# MCU063B_Emulator.net
KiCad netlist of a schematic drawn in Altium Designer
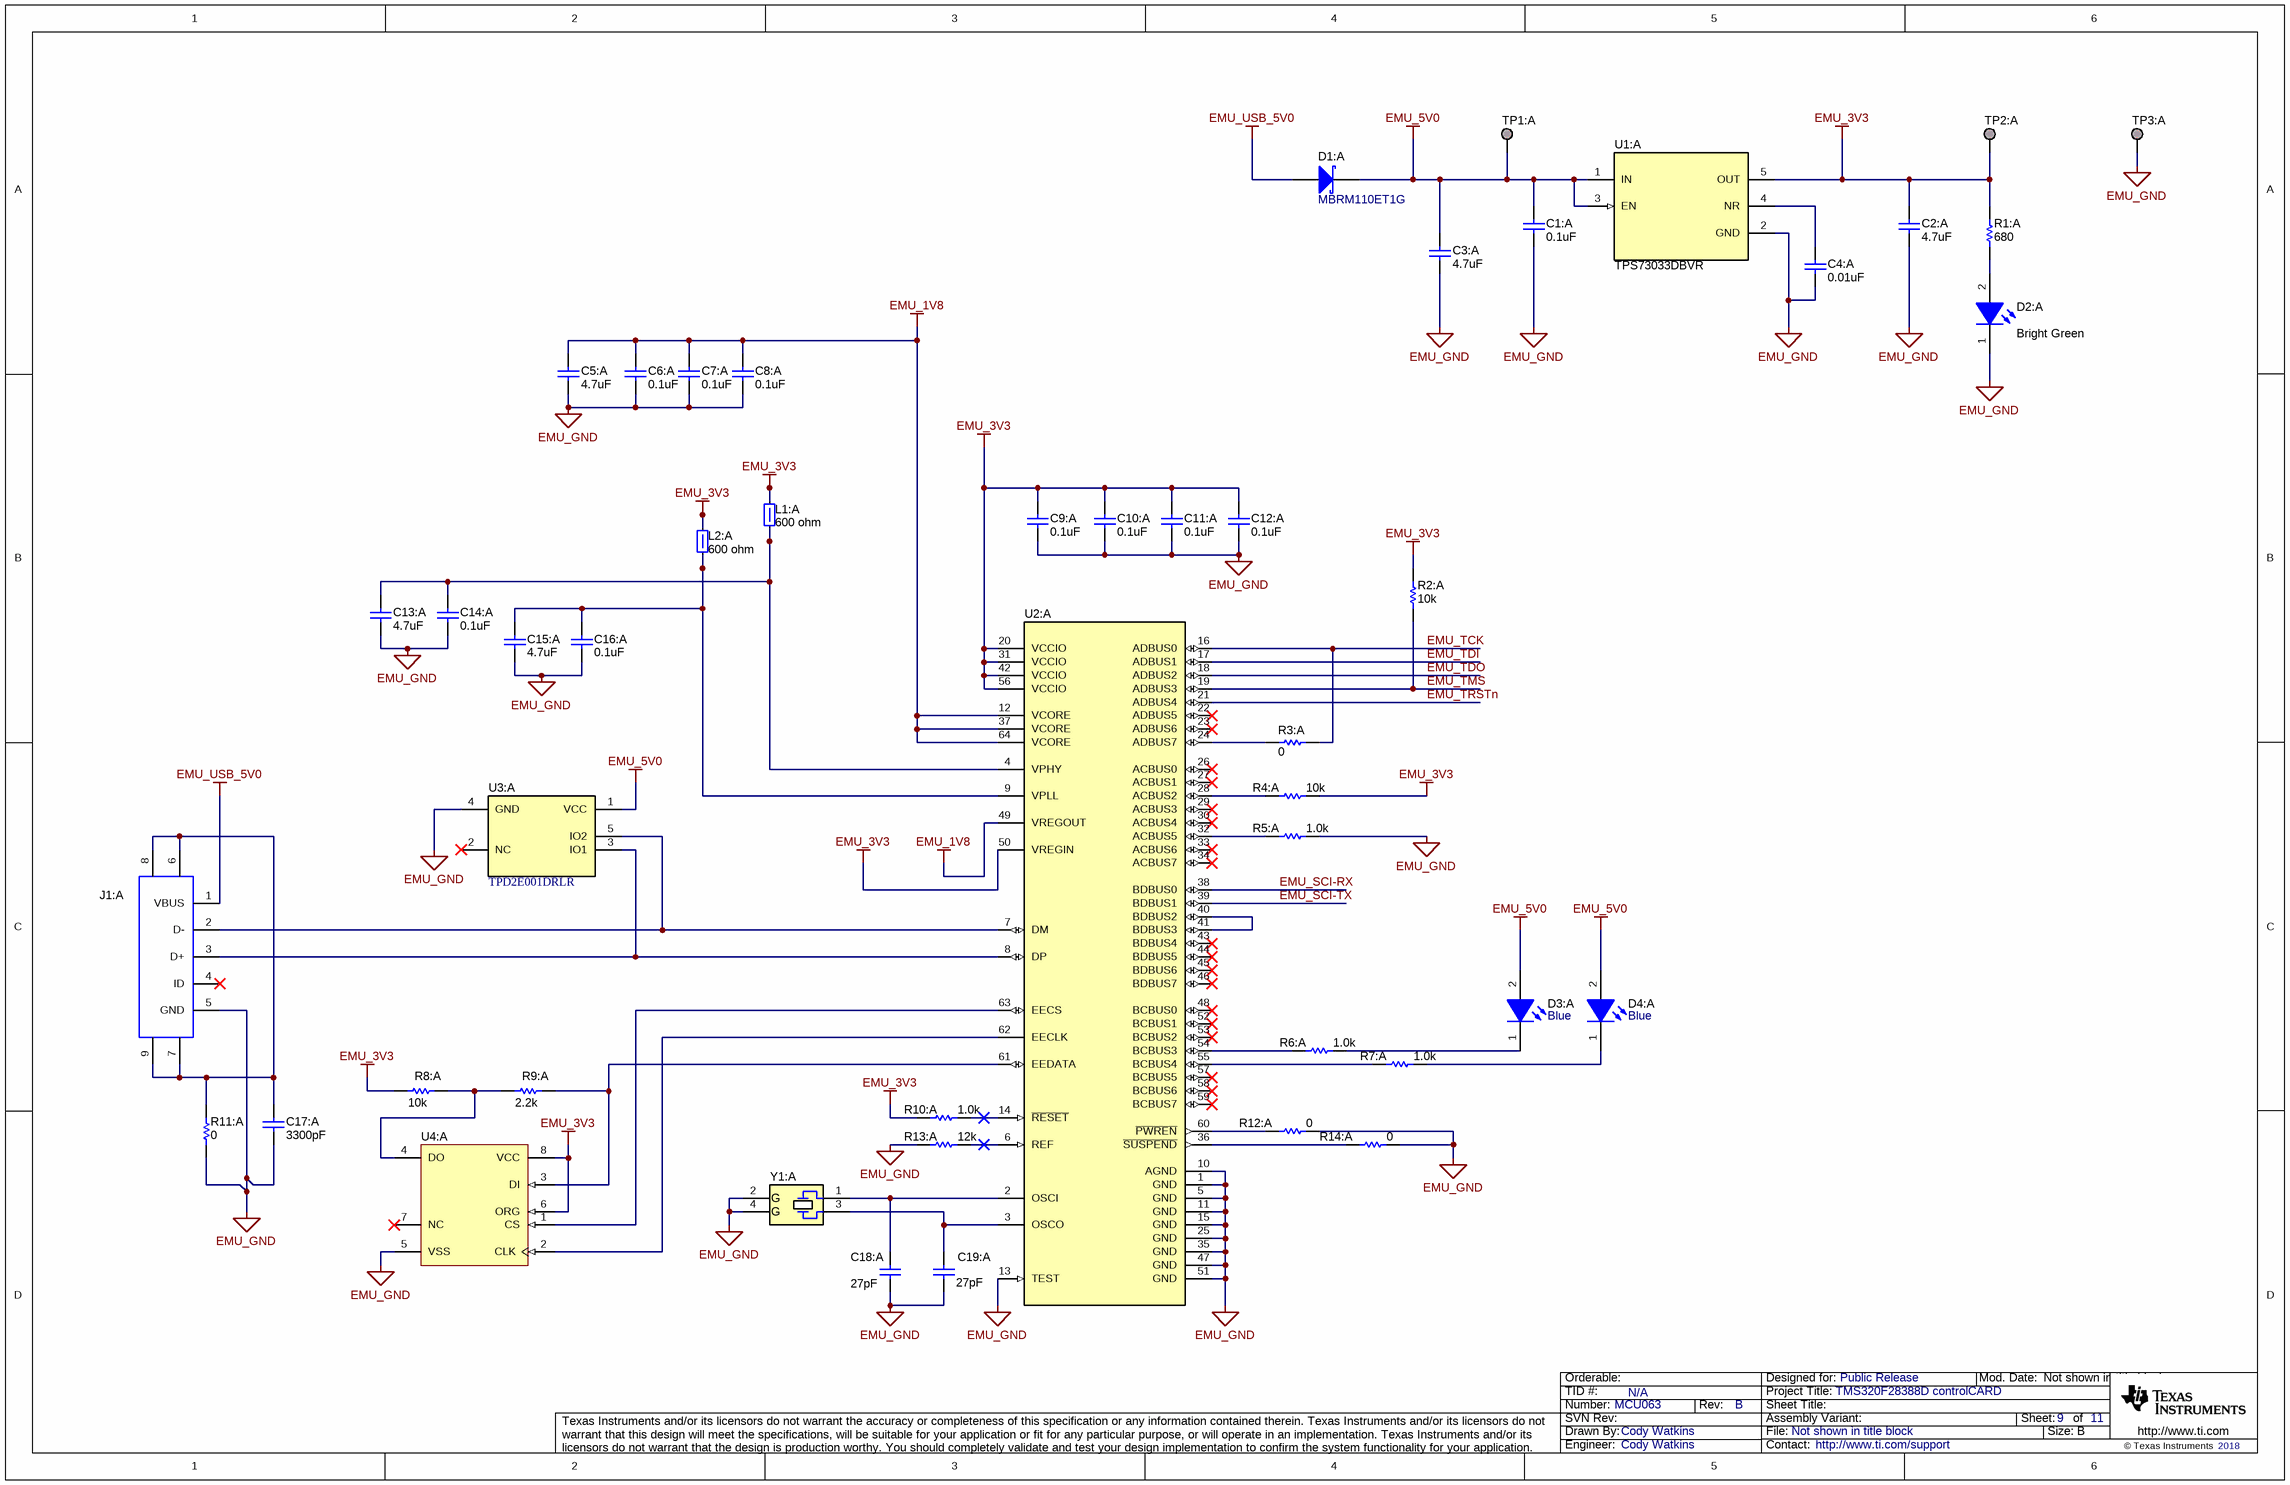
[diagram p0: MCU063B_Emulator.SchDoc]

(export (version "E")
  (design (tool "Eeschema 10.0.6"))
  (components
    (comp (ref "C1:A")
      (value "CL05B104KP5NNNC")
      (footprint "0402")
      (description "CAP, CERM, 0.1 uF, 10 V, +/- 10%, X7R, 0402")
      (fields
        (field (name "VALUEDISPLAYED") "0.1uF")
        (field (name "MANUFACTURER") "Samsung Electro-Mechanics")
        (field (name "PUBLISHER") "Texas Instruments")
      )
      (libsource (lib "Altium Vault - TI") (part "Capacitor"))
    )
    (comp (ref "C2:A")
      (value "C0603C475K9PACTU")
      (footprint "0603")
      (description "CAP, CERM, 4.7 uF, 6.3 V, +/- 10%, X5R, 0603")
      (fields
        (field (name "MANUFACTURER") "Kemet")
        (field (name "VALUEDISPLAYED") "4.7uF")
        (field (name "PUBLISHER") "Texas Instruments")
      )
      (libsource (lib "Altium Vault - TI") (part "Capacitor"))
    )
    (comp (ref "C3:A")
      (value "C0603C475K9PACTU")
      (footprint "0603")
      (description "CAP, CERM, 4.7 uF, 6.3 V, +/- 10%, X5R, 0603")
      (fields
        (field (name "MANUFACTURER") "Kemet")
        (field (name "VALUEDISPLAYED") "4.7uF")
        (field (name "PUBLISHER") "Texas Instruments")
      )
      (libsource (lib "Altium Vault - TI") (part "Capacitor"))
    )
    (comp (ref "C4:A")
      (value "0402ZC103KAT2A")
      (footprint "0402")
      (description "CAP, CERM, 0.01 uF, 10 V, +/- 10%, X7R, 0402")
      (fields
        (field (name "VALUEDISPLAYED") "0.01uF")
        (field (name "MANUFACTURER") "AVX")
        (field (name "PUBLISHER") "Texas Instruments")
      )
      (libsource (lib "Altium Vault - TI") (part "Capacitor"))
    )
    (comp (ref "C5:A")
      (value "C0603C475K9PACTU")
      (footprint "0603")
      (description "CAP, CERM, 4.7 uF, 6.3 V, +/- 10%, X5R, 0603")
      (fields
        (field (name "MANUFACTURER") "Kemet")
        (field (name "VALUEDISPLAYED") "4.7uF")
        (field (name "PUBLISHER") "Texas Instruments")
      )
      (libsource (lib "Altium Vault - TI") (part "Capacitor"))
    )
    (comp (ref "C6:A")
      (value "CL05B104KP5NNNC")
      (footprint "0402")
      (description "CAP, CERM, 0.1 uF, 10 V, +/- 10%, X7R, 0402")
      (fields
        (field (name "VALUEDISPLAYED") "0.1uF")
        (field (name "MANUFACTURER") "Samsung Electro-Mechanics")
        (field (name "PUBLISHER") "Texas Instruments")
      )
      (libsource (lib "Altium Vault - TI") (part "Capacitor"))
    )
    (comp (ref "C7:A")
      (value "CL05B104KP5NNNC")
      (footprint "0402")
      (description "CAP, CERM, 0.1 uF, 10 V, +/- 10%, X7R, 0402")
      (fields
        (field (name "VALUEDISPLAYED") "0.1uF")
        (field (name "MANUFACTURER") "Samsung Electro-Mechanics")
        (field (name "PUBLISHER") "Texas Instruments")
      )
      (libsource (lib "Altium Vault - TI") (part "Capacitor"))
    )
    (comp (ref "C8:A")
      (value "CL05B104KP5NNNC")
      (footprint "0402")
      (description "CAP, CERM, 0.1 uF, 10 V, +/- 10%, X7R, 0402")
      (fields
        (field (name "VALUEDISPLAYED") "0.1uF")
        (field (name "MANUFACTURER") "Samsung Electro-Mechanics")
        (field (name "PUBLISHER") "Texas Instruments")
      )
      (libsource (lib "Altium Vault - TI") (part "Capacitor"))
    )
    (comp (ref "C9:A")
      (value "CL05B104KP5NNNC")
      (footprint "0402")
      (description "CAP, CERM, 0.1 uF, 10 V, +/- 10%, X7R, 0402")
      (fields
        (field (name "VALUEDISPLAYED") "0.1uF")
        (field (name "MANUFACTURER") "Samsung Electro-Mechanics")
        (field (name "PUBLISHER") "Texas Instruments")
      )
      (libsource (lib "Altium Vault - TI") (part "Capacitor"))
    )
    (comp (ref "C10:A")
      (value "CL05B104KP5NNNC")
      (footprint "0402")
      (description "CAP, CERM, 0.1 uF, 10 V, +/- 10%, X7R, 0402")
      (fields
        (field (name "VALUEDISPLAYED") "0.1uF")
        (field (name "MANUFACTURER") "Samsung Electro-Mechanics")
        (field (name "PUBLISHER") "Texas Instruments")
      )
      (libsource (lib "Altium Vault - TI") (part "Capacitor"))
    )
    (comp (ref "C11:A")
      (value "CL05B104KP5NNNC")
      (footprint "0402")
      (description "CAP, CERM, 0.1 uF, 10 V, +/- 10%, X7R, 0402")
      (fields
        (field (name "VALUEDISPLAYED") "0.1uF")
        (field (name "MANUFACTURER") "Samsung Electro-Mechanics")
        (field (name "PUBLISHER") "Texas Instruments")
      )
      (libsource (lib "Altium Vault - TI") (part "Capacitor"))
    )
    (comp (ref "C12:A")
      (value "CL05B104KP5NNNC")
      (footprint "0402")
      (description "CAP, CERM, 0.1 uF, 10 V, +/- 10%, X7R, 0402")
      (fields
        (field (name "VALUEDISPLAYED") "0.1uF")
        (field (name "MANUFACTURER") "Samsung Electro-Mechanics")
        (field (name "PUBLISHER") "Texas Instruments")
      )
      (libsource (lib "Altium Vault - TI") (part "Capacitor"))
    )
    (comp (ref "C13:A")
      (value "C0603C475K9PACTU")
      (footprint "0603")
      (description "CAP, CERM, 4.7 uF, 6.3 V, +/- 10%, X5R, 0603")
      (fields
        (field (name "MANUFACTURER") "Kemet")
        (field (name "VALUEDISPLAYED") "4.7uF")
        (field (name "PUBLISHER") "Texas Instruments")
      )
      (libsource (lib "Altium Vault - TI") (part "Capacitor"))
    )
    (comp (ref "C14:A")
      (value "CL05B104KP5NNNC")
      (footprint "0402")
      (description "CAP, CERM, 0.1 uF, 10 V, +/- 10%, X7R, 0402")
      (fields
        (field (name "VALUEDISPLAYED") "0.1uF")
        (field (name "MANUFACTURER") "Samsung Electro-Mechanics")
        (field (name "PUBLISHER") "Texas Instruments")
      )
      (libsource (lib "Altium Vault - TI") (part "Capacitor"))
    )
    (comp (ref "C15:A")
      (value "C0603C475K9PACTU")
      (footprint "0603")
      (description "CAP, CERM, 4.7 uF, 6.3 V, +/- 10%, X5R, 0603")
      (fields
        (field (name "MANUFACTURER") "Kemet")
        (field (name "VALUEDISPLAYED") "4.7uF")
        (field (name "PUBLISHER") "Texas Instruments")
      )
      (libsource (lib "Altium Vault - TI") (part "Capacitor"))
    )
    (comp (ref "C16:A")
      (value "CL05B104KP5NNNC")
      (footprint "0402")
      (description "CAP, CERM, 0.1 uF, 10 V, +/- 10%, X7R, 0402")
      (fields
        (field (name "VALUEDISPLAYED") "0.1uF")
        (field (name "MANUFACTURER") "Samsung Electro-Mechanics")
        (field (name "PUBLISHER") "Texas Instruments")
      )
      (libsource (lib "Altium Vault - TI") (part "Capacitor"))
    )
    (comp (ref "C17:A")
      (value "CGA2B2X7R1H332K050BA")
      (footprint "0402")
      (description "CAP, CERM, 3300 pF, 50 V, +/- 10%, X7R, AEC-Q200 Grade 1, 0402")
      (fields
        (field (name "MANUFACTURER") "TDK")
        (field (name "VALUEDISPLAYED") "3300pF")
        (field (name "PUBLISHER") "Texas Instruments")
      )
      (libsource (lib "Altium Vault - TI") (part "Capacitor"))
    )
    (comp (ref "C18:A")
      (value "C0402C270J5GACTU")
      (footprint "0402")
      (description "CAP, CERM, 27 pF, 50 V,+/- 5%, C0G/NP0, 0402")
      (fields (field (name "VALUEDISPLAYED") "27pF") (field (name "MANUFACTURER") "Kemet"))
      (libsource (lib "Altium Vault - TI") (part "Capacitor"))
    )
    (comp (ref "C19:A")
      (value "C0402C270J5GACTU")
      (footprint "0402")
      (description "CAP, CERM, 27 pF, 50 V,+/- 5%, C0G/NP0, 0402")
      (fields (field (name "VALUEDISPLAYED") "27pF") (field (name "MANUFACTURER") "Kemet"))
      (libsource (lib "Altium Vault - TI") (part "Capacitor"))
    )
    (comp (ref "D1:A")
      (value "MBRM110ET1G")
      (footprint "POWERMITE")
      (description "Diode, Schottky, 10 V, 1 A, AEC-Q101, POWERMITE")
      (fields (field (name "MANUFACTURER") "ON Semiconductor"))
      (libsource (lib "Altium Vault - TI") (part "DIODE_SCHOTTKY"))
    )
    (comp (ref "D2:A")
      (value "Bright Green")
      (footprint "WL-SMCW_Green_0805")
      (description "LED, Bright Green, SMD")
      (fields
        (field (name "PARTNUMBER") "150080VS75000")
        (field (name "MANUFACTURER") "Wurth Elektronik")
        (field (name "PUBLISHER") "Texas Instruments")
      )
      (libsource (lib "Altium Vault - TI") (part "LED_A2_K1"))
    )
    (comp (ref "D3:A")
      (value "Blue")
      (footprint "WL-SMCW_Blue_0805")
      (description "LED, Blue, SMD")
      (fields (field (name "MANUFACTURER") "Wurth Elektronik") (field (name "PARTNUMBER") "150080BS75000"))
      (libsource (lib "Altium Vault - TI") (part "LED_A2_K1"))
    )
    (comp (ref "D4:A")
      (value "Blue")
      (footprint "WL-SMCW_Blue_0805")
      (description "LED, Blue, SMD")
      (fields (field (name "MANUFACTURER") "Wurth Elektronik") (field (name "PARTNUMBER") "150080BS75000"))
      (libsource (lib "Altium Vault - TI") (part "LED_A2_K1"))
    )
    (comp (ref "J1:A")
      (value "65100516121")
      (footprint "Wurth_65100516121")
      (description "Connector, Receptacle, USB Mini B 2.0, SMT")
      (fields (field (name "MANUFACTURER") "Wurth Elektronik") (field (name "PUBLISHER") "Texas Instruments"))
      (libsource (lib "Altium Vault - TI") (part "CONN_USB_5Pos-4Shld"))
    )
    (comp (ref "L1:A")
      (value "600 ohm")
      (footprint "0805_HV")
      (description "Ferrite Bead, 600 ohm @ 100 MHz, 0.5 A, 0805")
      (fields
        (field (name "PARTNUMBER") "HZ0805E601R-10")
        (field (name "MANUFACTURER") "Laird-Signal Integrity Products")
        (field (name "PUBLISHER") "Texas Instruments")
      )
      (libsource (lib "Altium Vault - TI") (part "Ferrite_Bead"))
    )
    (comp (ref "L2:A")
      (value "600 ohm")
      (footprint "0805_HV")
      (description "Ferrite Bead, 600 ohm @ 100 MHz, 0.5 A, 0805")
      (fields
        (field (name "PARTNUMBER") "HZ0805E601R-10")
        (field (name "MANUFACTURER") "Laird-Signal Integrity Products")
        (field (name "PUBLISHER") "Texas Instruments")
      )
      (libsource (lib "Altium Vault - TI") (part "Ferrite_Bead"))
    )
    (comp (ref "R1:A")
      (value "CRCW0402680RJNED")
      (footprint "0402")
      (description "RES, 680, 5%, 0.063 W, AEC-Q200 Grade 0, 0402")
      (fields (field (name "VALUEDISPLAYED") "680") (field (name "MANUFACTURER") "Vishay-Dale"))
      (libsource (lib "Altium Vault - TI") (part "Resistor"))
    )
    (comp (ref "R2:A")
      (value "CRCW040210K0JNED")
      (footprint "0402")
      (description "RES, 10 k, 5%, 0.063 W, AEC-Q200 Grade 0, 0402")
      (fields (field (name "VALUEDISPLAYED") "10k") (field (name "MANUFACTURER") "Vishay-Dale"))
      (libsource (lib "Altium Vault - TI") (part "Resistor"))
    )
    (comp (ref "R3:A")
      (value "CRCW04020000Z0ED")
      (footprint "0402")
      (description "RES, 0, 5%, 0.063 W, AEC-Q200 Grade 0, 0402")
      (fields (field (name "VALUEDISPLAYED") "0") (field (name "MANUFACTURER") "Vishay-Dale"))
      (libsource (lib "Altium Vault - TI") (part "Resistor"))
    )
    (comp (ref "R4:A")
      (value "CRCW040210K0JNED")
      (footprint "0402")
      (description "RES, 10 k, 5%, 0.063 W, AEC-Q200 Grade 0, 0402")
      (fields (field (name "VALUEDISPLAYED") "10k") (field (name "MANUFACTURER") "Vishay-Dale"))
      (libsource (lib "Altium Vault - TI") (part "Resistor"))
    )
    (comp (ref "R5:A")
      (value "CRCW04021K00JNED")
      (footprint "0402")
      (description "RES, 1.0 k, 5%, 0.063 W, AEC-Q200 Grade 0, 0402")
      (fields (field (name "VALUEDISPLAYED") "1.0k") (field (name "MANUFACTURER") "Vishay-Dale"))
      (libsource (lib "Altium Vault - TI") (part "Resistor"))
    )
    (comp (ref "R6:A")
      (value "CRCW04021K00JNED")
      (footprint "0402")
      (description "RES, 1.0 k, 5%, 0.063 W, AEC-Q200 Grade 0, 0402")
      (fields (field (name "VALUEDISPLAYED") "1.0k") (field (name "MANUFACTURER") "Vishay-Dale"))
      (libsource (lib "Altium Vault - TI") (part "Resistor"))
    )
    (comp (ref "R7:A")
      (value "CRCW04021K00JNED")
      (footprint "0402")
      (description "RES, 1.0 k, 5%, 0.063 W, AEC-Q200 Grade 0, 0402")
      (fields (field (name "VALUEDISPLAYED") "1.0k") (field (name "MANUFACTURER") "Vishay-Dale"))
      (libsource (lib "Altium Vault - TI") (part "Resistor"))
    )
    (comp (ref "R8:A")
      (value "CRCW040210K0JNED")
      (footprint "0402")
      (description "RES, 10 k, 5%, 0.063 W, AEC-Q200 Grade 0, 0402")
      (fields (field (name "VALUEDISPLAYED") "10k") (field (name "MANUFACTURER") "Vishay-Dale"))
      (libsource (lib "Altium Vault - TI") (part "Resistor"))
    )
    (comp (ref "R9:A")
      (value "CRCW04022K20JNED")
      (footprint "0402")
      (description "RES, 2.2 k, 5%, 0.063 W, AEC-Q200 Grade 0, 0402")
      (fields (field (name "VALUEDISPLAYED") "2.2k") (field (name "MANUFACTURER") "Vishay-Dale"))
      (libsource (lib "Altium Vault - TI") (part "Resistor"))
    )
    (comp (ref "R10:A")
      (value "CRCW04021K00JNED")
      (footprint "0402")
      (description "RES, 1.0 k, 5%, 0.063 W, AEC-Q200 Grade 0, 0402")
      (fields (field (name "VALUEDISPLAYED") "1.0k") (field (name "MANUFACTURER") "Vishay-Dale"))
      (libsource (lib "Altium Vault - TI") (part "Resistor"))
    )
    (comp (ref "R11:A")
      (value "CRCW04020000Z0ED")
      (footprint "0402")
      (description "RES, 0, 5%, 0.063 W, AEC-Q200 Grade 0, 0402")
      (fields (field (name "VALUEDISPLAYED") "0") (field (name "MANUFACTURER") "Vishay-Dale"))
      (libsource (lib "Altium Vault - TI") (part "Resistor"))
    )
    (comp (ref "R12:A")
      (value "CRCW04020000Z0ED")
      (footprint "0402")
      (description "RES, 0, 5%, 0.063 W, AEC-Q200 Grade 0, 0402")
      (fields (field (name "VALUEDISPLAYED") "0") (field (name "MANUFACTURER") "Vishay-Dale"))
      (libsource (lib "Altium Vault - TI") (part "Resistor"))
    )
    (comp (ref "R13:A")
      (value "CRCW040212K0JNED")
      (footprint "0402")
      (description "RES, 12 k, 5%, 0.063 W, AEC-Q200 Grade 0, 0402")
      (fields (field (name "VALUEDISPLAYED") "12k") (field (name "MANUFACTURER") "Vishay-Dale"))
      (libsource (lib "Altium Vault - TI") (part "Resistor"))
    )
    (comp (ref "R14:A")
      (value "CRCW04020000Z0ED")
      (footprint "0402")
      (description "RES, 0, 5%, 0.063 W, AEC-Q200 Grade 0, 0402")
      (fields (field (name "VALUEDISPLAYED") "0") (field (name "MANUFACTURER") "Vishay-Dale"))
      (libsource (lib "Altium Vault - TI") (part "Resistor"))
    )
    (comp (ref "TP1:A")
      (value "TESTPOINT")
      (footprint "TP_50MIL-25MILHOLE")
      (description "TEST POINT.  No entry in BOM.")
      (libsource (lib "Altium Vault - TI") (part "TESTPOINT"))
    )
    (comp (ref "TP2:A")
      (value "TESTPOINT")
      (footprint "TP_50MIL-25MILHOLE")
      (description "TEST POINT.  No entry in BOM.")
      (libsource (lib "Altium Vault - TI") (part "TESTPOINT"))
    )
    (comp (ref "TP3:A")
      (value "TESTPOINT")
      (footprint "TP_50MIL-25MILHOLE")
      (description "TEST POINT.  No entry in BOM.")
      (libsource (lib "Altium Vault - TI") (part "TESTPOINT"))
    )
    (comp (ref "U1:A")
      (value "TPS73033DBVR")
      (footprint "DBV0005A_N")
      (description "Low-Noise, High PSRR, RF 200-mA Low-Dropout Linear Regulators, DBV0005A (SOT-23-5)")
      (fields
        (field (name "ALTERNATE PARTNUMBER") "TPS73033DBVT")
        (field (name "MANUFACTURER") "Texas Instruments")
        (field (name "PUBLISHER") "Texas Instruments")
      )
      (libsource (lib "Altium Vault - TI") (part "TPS730XXDBV"))
    )
    (comp (ref "U2:A")
      (value "FT2232HL-REEL")
      (footprint "LQFP64_N")
      (description "Dual High Speed USB To Multipurpose UART/FIFO IC, LQFP-64")
      (fields (field (name "MANUFACTURER") "FTDI") (field (name "PUBLISHER") "Texas Instruments"))
      (libsource (lib "Altium Vault - TI") (part "CMP-0004796-1"))
    )
    (comp (ref "U3:A")
      (value "TPD2E001DRLR")
      (footprint "DRL0005A")
      (fields (field (name "MANUFACTURER") "Texas Instruments"))
      (libsource (lib "Altium Vault - TI") (part "TI-TPD2E001-Q1-SOT_DRL-5"))
    )
    (comp (ref "U4:A")
      (value "93LC56C-I/SN")
      (footprint "SOIC-8")
      (description "2K Microwire Compatible Serial EEPROM, SOIC-8")
      (fields (field (name "MANUFACTURER") "Microchip") (field (name "PUBLISHER") "Texas Instruments"))
      (libsource (lib "Altium Vault - TI") (part "93LC46C-SN"))
    )
    (comp (ref "Y1:A")
      (value "ECS-120-20-30B-TR")
      (footprint "ECS_ECX-53B")
      (description "Crystal, 12 MHz, 20pF, SMD")
      (fields (field (name "MANUFACTURER") "ECS Inc."))
      (libsource (lib "Altium Vault - TI") (part "CMP-0004646-3"))
    )
  )
  (nets
    (net (code "1") (name "/EMU_SCI-RX") (class "Default")
      (node (ref "U2:A") (pin "38") (pinfunction "BDBUS0_38") (pintype "bidirectional"))
    )
    (net (code "2") (name "/EMU_SCI-TX") (class "Default")
      (node (ref "U2:A") (pin "39") (pinfunction "BDBUS1_39") (pintype "bidirectional"))
    )
    (net (code "3") (name "/EMU_TCK") (class "Default")
      (node (ref "R3:A") (pin "1") (pinfunction "1_1") (pintype "passive"))
      (node (ref "U2:A") (pin "16") (pinfunction "ADBUS0_16") (pintype "bidirectional"))
    )
    (net (code "4") (name "/EMU_TDI") (class "Default")
      (node (ref "U2:A") (pin "17") (pinfunction "ADBUS1_17") (pintype "bidirectional"))
    )
    (net (code "5") (name "/EMU_TDO") (class "Default")
      (node (ref "U2:A") (pin "18") (pinfunction "ADBUS2_18") (pintype "bidirectional"))
    )
    (net (code "6") (name "/EMU_TMS") (class "Default")
      (node (ref "R2:A") (pin "1") (pinfunction "1_1") (pintype "passive"))
      (node (ref "U2:A") (pin "19") (pinfunction "ADBUS3_19") (pintype "bidirectional"))
    )
    (net (code "7") (name "/EMU_TRSTn") (class "Default")
      (node (ref "U2:A") (pin "21") (pinfunction "ADBUS4_21") (pintype "bidirectional"))
    )
    (net (code "8") (name "EMU_1V8") (class "Default")
      (node (ref "C5:A") (pin "2") (pinfunction "2_2") (pintype "passive"))
      (node (ref "C6:A") (pin "2") (pinfunction "2_2") (pintype "passive"))
      (node (ref "C7:A") (pin "2") (pinfunction "2_2") (pintype "passive"))
      (node (ref "C8:A") (pin "2") (pinfunction "2_2") (pintype "passive"))
      (node (ref "U2:A") (pin "12") (pinfunction "VCORE_12") (pintype "power_in"))
      (node (ref "U2:A") (pin "37") (pinfunction "VCORE_37") (pintype "power_in"))
      (node (ref "U2:A") (pin "49") (pinfunction "VREGOUT_49") (pintype "power_in"))
      (node (ref "U2:A") (pin "64") (pinfunction "VCORE_64") (pintype "power_in"))
    )
    (net (code "9") (name "EMU_3V3") (class "Default")
      (node (ref "C10:A") (pin "2") (pinfunction "2_2") (pintype "passive"))
      (node (ref "C11:A") (pin "2") (pinfunction "2_2") (pintype "passive"))
      (node (ref "C12:A") (pin "2") (pinfunction "2_2") (pintype "passive"))
      (node (ref "C2:A") (pin "1") (pinfunction "1_1") (pintype "passive"))
      (node (ref "C9:A") (pin "2") (pinfunction "2_2") (pintype "passive"))
      (node (ref "L1:A") (pin "2") (pinfunction "2_2") (pintype "passive"))
      (node (ref "L2:A") (pin "2") (pinfunction "2_2") (pintype "passive"))
      (node (ref "R10:A") (pin "1") (pinfunction "1_1") (pintype "passive"))
      (node (ref "R1:A") (pin "1") (pinfunction "1_1") (pintype "passive"))
      (node (ref "R2:A") (pin "2") (pinfunction "2_2") (pintype "passive"))
      (node (ref "R4:A") (pin "2") (pinfunction "2_2") (pintype "passive"))
      (node (ref "R8:A") (pin "1") (pinfunction "1_1") (pintype "passive"))
      (node (ref "TP2:A") (pin "1") (pintype "passive"))
      (node (ref "U1:A") (pin "5") (pinfunction "OUT_5") (pintype "power_in"))
      (node (ref "U2:A") (pin "20") (pinfunction "VCCIO_20") (pintype "power_in"))
      (node (ref "U2:A") (pin "31") (pinfunction "VCCIO_31") (pintype "power_in"))
      (node (ref "U2:A") (pin "42") (pinfunction "VCCIO_42") (pintype "power_in"))
      (node (ref "U2:A") (pin "50") (pinfunction "VREGIN_50") (pintype "power_in"))
      (node (ref "U2:A") (pin "56") (pinfunction "VCCIO_56") (pintype "power_in"))
      (node (ref "U4:A") (pin "6") (pinfunction "ORG_6") (pintype "input"))
      (node (ref "U4:A") (pin "8") (pinfunction "VCC_8") (pintype "power_in"))
    )
    (net (code "10") (name "EMU_5V0") (class "Default")
      (node (ref "C1:A") (pin "2") (pinfunction "2_2") (pintype "passive"))
      (node (ref "C3:A") (pin "1") (pinfunction "1_1") (pintype "passive"))
      (node (ref "D1:A") (pin "1") (pinfunction "K_1") (pintype "passive"))
      (node (ref "D3:A") (pin "2") (pinfunction "A_2") (pintype "passive"))
      (node (ref "D4:A") (pin "2") (pinfunction "A_2") (pintype "passive"))
      (node (ref "TP1:A") (pin "1") (pintype "passive"))
      (node (ref "U1:A") (pin "1") (pinfunction "IN_1") (pintype "power_in"))
      (node (ref "U1:A") (pin "3") (pinfunction "EN_3") (pintype "input"))
      (node (ref "U3:A") (pin "1") (pinfunction "VCC_1") (pintype "power_in"))
    )
    (net (code "11") (name "EMU_GND") (class "Default")
      (node (ref "C10:A") (pin "1") (pinfunction "1_1") (pintype "passive"))
      (node (ref "C11:A") (pin "1") (pinfunction "1_1") (pintype "passive"))
      (node (ref "C12:A") (pin "1") (pinfunction "1_1") (pintype "passive"))
      (node (ref "C13:A") (pin "2") (pinfunction "2_2") (pintype "passive"))
      (node (ref "C14:A") (pin "1") (pinfunction "1_1") (pintype "passive"))
      (node (ref "C15:A") (pin "2") (pinfunction "2_2") (pintype "passive"))
      (node (ref "C16:A") (pin "1") (pinfunction "1_1") (pintype "passive"))
      (node (ref "C17:A") (pin "1") (pinfunction "1_1") (pintype "passive"))
      (node (ref "C18:A") (pin "1") (pinfunction "1_1") (pintype "passive"))
      (node (ref "C19:A") (pin "1") (pinfunction "1_1") (pintype "passive"))
      (node (ref "C1:A") (pin "1") (pinfunction "1_1") (pintype "passive"))
      (node (ref "C2:A") (pin "2") (pinfunction "2_2") (pintype "passive"))
      (node (ref "C3:A") (pin "2") (pinfunction "2_2") (pintype "passive"))
      (node (ref "C4:A") (pin "1") (pinfunction "1_1") (pintype "passive"))
      (node (ref "C5:A") (pin "1") (pinfunction "1_1") (pintype "passive"))
      (node (ref "C6:A") (pin "1") (pinfunction "1_1") (pintype "passive"))
      (node (ref "C7:A") (pin "1") (pinfunction "1_1") (pintype "passive"))
      (node (ref "C8:A") (pin "1") (pinfunction "1_1") (pintype "passive"))
      (node (ref "C9:A") (pin "1") (pinfunction "1_1") (pintype "passive"))
      (node (ref "D2:A") (pin "1") (pinfunction "K_1") (pintype "passive"))
      (node (ref "J1:A") (pin "5") (pinfunction "GND_5") (pintype "passive"))
      (node (ref "R11:A") (pin "2") (pinfunction "2_2") (pintype "passive"))
      (node (ref "R12:A") (pin "1") (pinfunction "1_1") (pintype "passive"))
      (node (ref "R13:A") (pin "1") (pinfunction "1_1") (pintype "passive"))
      (node (ref "R14:A") (pin "1") (pinfunction "1_1") (pintype "passive"))
      (node (ref "R5:A") (pin "2") (pinfunction "2_2") (pintype "passive"))
      (node (ref "TP3:A") (pin "1") (pintype "passive"))
      (node (ref "U1:A") (pin "2") (pinfunction "GND_2") (pintype "power_in"))
      (node (ref "U2:A") (pin "1") (pinfunction "GND_1") (pintype "power_in"))
      (node (ref "U2:A") (pin "10") (pinfunction "AGND_10") (pintype "power_in"))
      (node (ref "U2:A") (pin "11") (pinfunction "GND_11") (pintype "power_in"))
      (node (ref "U2:A") (pin "13") (pinfunction "TEST_13") (pintype "input"))
      (node (ref "U2:A") (pin "15") (pinfunction "GND_15") (pintype "power_in"))
      (node (ref "U2:A") (pin "25") (pinfunction "GND_25") (pintype "power_in"))
      (node (ref "U2:A") (pin "35") (pinfunction "GND_35") (pintype "power_in"))
      (node (ref "U2:A") (pin "47") (pinfunction "GND_47") (pintype "power_in"))
      (node (ref "U2:A") (pin "5") (pinfunction "GND_5") (pintype "power_in"))
      (node (ref "U2:A") (pin "51") (pinfunction "GND_51") (pintype "power_in"))
      (node (ref "U3:A") (pin "4") (pinfunction "GND_4") (pintype "power_in"))
      (node (ref "U4:A") (pin "5") (pinfunction "VSS_5") (pintype "power_in"))
      (node (ref "Y1:A") (pin "2") (pinfunction "GND_2") (pintype "power_in"))
      (node (ref "Y1:A") (pin "4") (pinfunction "GND_4") (pintype "power_in"))
    )
    (net (code "12") (name "EMU_USB_5V0") (class "Default")
      (node (ref "D1:A") (pin "2") (pinfunction "A_2") (pintype "passive"))
      (node (ref "J1:A") (pin "1") (pinfunction "VBUS_1") (pintype "passive"))
    )
    (net (code "13") (name "Net-(C17:A-Pad2)") (class "Default")
      (node (ref "C17:A") (pin "2") (pinfunction "2_2") (pintype "passive"))
      (node (ref "J1:A") (pin "6") (pinfunction "6_6") (pintype "passive"))
      (node (ref "J1:A") (pin "7") (pinfunction "7_7") (pintype "passive"))
      (node (ref "J1:A") (pin "8") (pinfunction "8_8") (pintype "passive"))
      (node (ref "J1:A") (pin "9") (pinfunction "9_9") (pintype "passive"))
      (node (ref "R11:A") (pin "1") (pinfunction "1_1") (pintype "passive"))
    )
    (net (code "14") (name "Net-(D2:A-A)") (class "Default")
      (node (ref "D2:A") (pin "2") (pinfunction "A_2") (pintype "passive"))
      (node (ref "R1:A") (pin "2") (pinfunction "2_2") (pintype "passive"))
    )
    (net (code "15") (name "Net-(D3:A-K)") (class "Default")
      (node (ref "D3:A") (pin "1") (pinfunction "K_1") (pintype "passive"))
      (node (ref "R6:A") (pin "2") (pinfunction "2_2") (pintype "passive"))
    )
    (net (code "16") (name "Net-(D4:A-K)") (class "Default")
      (node (ref "D4:A") (pin "1") (pinfunction "K_1") (pintype "passive"))
      (node (ref "R7:A") (pin "2") (pinfunction "2_2") (pintype "passive"))
    )
    (net (code "17") (name "Net-(J1:A-D+)") (class "Default")
      (node (ref "J1:A") (pin "3") (pinfunction "D+_3") (pintype "passive"))
      (node (ref "U2:A") (pin "8") (pinfunction "DP_8") (pintype "bidirectional"))
      (node (ref "U3:A") (pin "3") (pinfunction "IO1_3") (pintype "passive"))
    )
    (net (code "18") (name "Net-(J1:A-D-)") (class "Default")
      (node (ref "J1:A") (pin "2") (pinfunction "D-_2") (pintype "passive"))
      (node (ref "U2:A") (pin "7") (pinfunction "DM_7") (pintype "bidirectional"))
      (node (ref "U3:A") (pin "5") (pinfunction "IO2_5") (pintype "passive"))
    )
    (net (code "19") (name "Net-(U1:A-NR)") (class "Default")
      (node (ref "C4:A") (pin "2") (pinfunction "2_2") (pintype "passive"))
      (node (ref "U1:A") (pin "4") (pinfunction "NR_4") (pintype "passive"))
    )
    (net (code "20") (name "Net-(U2:A-ACBUS2)") (class "Default")
      (node (ref "R4:A") (pin "1") (pinfunction "1_1") (pintype "passive"))
      (node (ref "U2:A") (pin "28") (pinfunction "ACBUS2_28") (pintype "bidirectional"))
    )
    (net (code "21") (name "Net-(U2:A-ACBUS5)") (class "Default")
      (node (ref "R5:A") (pin "1") (pinfunction "1_1") (pintype "passive"))
      (node (ref "U2:A") (pin "32") (pinfunction "ACBUS5_32") (pintype "bidirectional"))
    )
    (net (code "22") (name "Net-(U2:A-ADBUS7)") (class "Default")
      (node (ref "R3:A") (pin "2") (pinfunction "2_2") (pintype "passive"))
      (node (ref "U2:A") (pin "24") (pinfunction "ADBUS7_24") (pintype "bidirectional"))
    )
    (net (code "23") (name "Net-(U2:A-BCBUS3)") (class "Default")
      (node (ref "R6:A") (pin "1") (pinfunction "1_1") (pintype "passive"))
      (node (ref "U2:A") (pin "54") (pinfunction "BCBUS3_54") (pintype "bidirectional"))
    )
    (net (code "24") (name "Net-(U2:A-BCBUS4)") (class "Default")
      (node (ref "R7:A") (pin "1") (pinfunction "1_1") (pintype "passive"))
      (node (ref "U2:A") (pin "55") (pinfunction "BCBUS4_55") (pintype "bidirectional"))
    )
    (net (code "25") (name "Net-(U2:A-BDBUS2)") (class "Default")
      (node (ref "U2:A") (pin "40") (pinfunction "BDBUS2_40") (pintype "bidirectional"))
      (node (ref "U2:A") (pin "41") (pinfunction "BDBUS3_41") (pintype "bidirectional"))
    )
    (net (code "26") (name "Net-(U2:A-EECLK)") (class "Default")
      (node (ref "U2:A") (pin "62") (pinfunction "EECLK_62") (pintype "tri_state"))
      (node (ref "U4:A") (pin "2") (pinfunction "CLK_2") (pintype "input"))
    )
    (net (code "27") (name "Net-(U2:A-EECS)") (class "Default")
      (node (ref "U2:A") (pin "63") (pinfunction "EECS_63") (pintype "bidirectional"))
      (node (ref "U4:A") (pin "1") (pinfunction "CS_1") (pintype "input"))
    )
    (net (code "28") (name "Net-(U2:A-EEDATA)") (class "Default")
      (node (ref "R9:A") (pin "2") (pinfunction "2_2") (pintype "passive"))
      (node (ref "U2:A") (pin "61") (pinfunction "EEDATA_61") (pintype "bidirectional"))
      (node (ref "U4:A") (pin "3") (pinfunction "DI_3") (pintype "input"))
    )
    (net (code "29") (name "Net-(U2:A-OSCI)") (class "Default")
      (node (ref "C18:A") (pin "2") (pinfunction "2_2") (pintype "passive"))
      (node (ref "U2:A") (pin "2") (pinfunction "OSCI_2") (pintype "passive"))
      (node (ref "Y1:A") (pin "1") (pinfunction "1_1") (pintype "passive"))
    )
    (net (code "30") (name "Net-(U2:A-OSCO)") (class "Default")
      (node (ref "C19:A") (pin "2") (pinfunction "2_2") (pintype "passive"))
      (node (ref "U2:A") (pin "3") (pinfunction "OSCO_3") (pintype "passive"))
      (node (ref "Y1:A") (pin "3") (pinfunction "3_3") (pintype "passive"))
    )
    (net (code "31") (name "Net-(U2:A-REF)") (class "Default")
      (node (ref "R13:A") (pin "2") (pinfunction "2_2") (pintype "passive"))
      (node (ref "U2:A") (pin "6") (pinfunction "REF_6") (pintype "input"))
    )
    (net (code "32") (name "Net-(U2:A-VPHY)") (class "Default")
      (node (ref "C13:A") (pin "1") (pinfunction "1_1") (pintype "passive"))
      (node (ref "C14:A") (pin "2") (pinfunction "2_2") (pintype "passive"))
      (node (ref "L1:A") (pin "1") (pinfunction "1_1") (pintype "passive"))
      (node (ref "U2:A") (pin "4") (pinfunction "VPHY_4") (pintype "power_in"))
    )
    (net (code "33") (name "Net-(U2:A-VPLL)") (class "Default")
      (node (ref "C15:A") (pin "1") (pinfunction "1_1") (pintype "passive"))
      (node (ref "C16:A") (pin "2") (pinfunction "2_2") (pintype "passive"))
      (node (ref "L2:A") (pin "1") (pinfunction "1_1") (pintype "passive"))
      (node (ref "U2:A") (pin "9") (pinfunction "VPLL_9") (pintype "power_in"))
    )
    (net (code "34") (name "Net-(U2:A-~{PWREN})") (class "Default")
      (node (ref "R12:A") (pin "2") (pinfunction "2_2") (pintype "passive"))
      (node (ref "U2:A") (pin "60") (pinfunction "~{PWREN}_60") (pintype "output"))
    )
    (net (code "35") (name "Net-(U2:A-~{RESET})") (class "Default")
      (node (ref "R10:A") (pin "2") (pinfunction "2_2") (pintype "passive"))
      (node (ref "U2:A") (pin "14") (pinfunction "~{RESET}_14") (pintype "input"))
    )
    (net (code "36") (name "Net-(U2:A-~{SUSPEND})") (class "Default")
      (node (ref "R14:A") (pin "2") (pinfunction "2_2") (pintype "passive"))
      (node (ref "U2:A") (pin "36") (pinfunction "~{SUSPEND}_36") (pintype "output"))
    )
    (net (code "37") (name "Net-(U4:A-DO)") (class "Default")
      (node (ref "R8:A") (pin "2") (pinfunction "2_2") (pintype "passive"))
      (node (ref "R9:A") (pin "1") (pinfunction "1_1") (pintype "passive"))
      (node (ref "U4:A") (pin "4") (pinfunction "DO_4") (pintype "tri_state"))
    )
    (net (code "38") (name "unconnected-(J1:A-ID-Pad4)") (class "Default")
      (node (ref "J1:A") (pin "4") (pinfunction "ID_4") (pintype "passive+no_connect"))
    )
    (net (code "39") (name "unconnected-(U2:A-ACBUS0-Pad26)") (class "Default")
      (node (ref "U2:A") (pin "26") (pinfunction "ACBUS0_26") (pintype "bidirectional+no_connect"))
    )
    (net (code "40") (name "unconnected-(U2:A-ACBUS1-Pad27)") (class "Default")
      (node (ref "U2:A") (pin "27") (pinfunction "ACBUS1_27") (pintype "bidirectional+no_connect"))
    )
    (net (code "41") (name "unconnected-(U2:A-ACBUS3-Pad29)") (class "Default")
      (node (ref "U2:A") (pin "29") (pinfunction "ACBUS3_29") (pintype "bidirectional+no_connect"))
    )
    (net (code "42") (name "unconnected-(U2:A-ACBUS4-Pad30)") (class "Default")
      (node (ref "U2:A") (pin "30") (pinfunction "ACBUS4_30") (pintype "bidirectional+no_connect"))
    )
    (net (code "43") (name "unconnected-(U2:A-ACBUS6-Pad33)") (class "Default")
      (node (ref "U2:A") (pin "33") (pinfunction "ACBUS6_33") (pintype "bidirectional+no_connect"))
    )
    (net (code "44") (name "unconnected-(U2:A-ACBUS7-Pad34)") (class "Default")
      (node (ref "U2:A") (pin "34") (pinfunction "ACBUS7_34") (pintype "bidirectional+no_connect"))
    )
    (net (code "45") (name "unconnected-(U2:A-ADBUS5-Pad22)") (class "Default")
      (node (ref "U2:A") (pin "22") (pinfunction "ADBUS5_22") (pintype "bidirectional+no_connect"))
    )
    (net (code "46") (name "unconnected-(U2:A-ADBUS6-Pad23)") (class "Default")
      (node (ref "U2:A") (pin "23") (pinfunction "ADBUS6_23") (pintype "bidirectional+no_connect"))
    )
    (net (code "47") (name "unconnected-(U2:A-BCBUS0-Pad48)") (class "Default")
      (node (ref "U2:A") (pin "48") (pinfunction "BCBUS0_48") (pintype "bidirectional+no_connect"))
    )
    (net (code "48") (name "unconnected-(U2:A-BCBUS1-Pad52)") (class "Default")
      (node (ref "U2:A") (pin "52") (pinfunction "BCBUS1_52") (pintype "bidirectional+no_connect"))
    )
    (net (code "49") (name "unconnected-(U2:A-BCBUS2-Pad53)") (class "Default")
      (node (ref "U2:A") (pin "53") (pinfunction "BCBUS2_53") (pintype "bidirectional+no_connect"))
    )
    (net (code "50") (name "unconnected-(U2:A-BCBUS5-Pad57)") (class "Default")
      (node (ref "U2:A") (pin "57") (pinfunction "BCBUS5_57") (pintype "bidirectional+no_connect"))
    )
    (net (code "51") (name "unconnected-(U2:A-BCBUS6-Pad58)") (class "Default")
      (node (ref "U2:A") (pin "58") (pinfunction "BCBUS6_58") (pintype "bidirectional+no_connect"))
    )
    (net (code "52") (name "unconnected-(U2:A-BCBUS7-Pad59)") (class "Default")
      (node (ref "U2:A") (pin "59") (pinfunction "BCBUS7_59") (pintype "bidirectional+no_connect"))
    )
    (net (code "53") (name "unconnected-(U2:A-BDBUS4-Pad43)") (class "Default")
      (node (ref "U2:A") (pin "43") (pinfunction "BDBUS4_43") (pintype "bidirectional+no_connect"))
    )
    (net (code "54") (name "unconnected-(U2:A-BDBUS5-Pad44)") (class "Default")
      (node (ref "U2:A") (pin "44") (pinfunction "BDBUS5_44") (pintype "bidirectional+no_connect"))
    )
    (net (code "55") (name "unconnected-(U2:A-BDBUS6-Pad45)") (class "Default")
      (node (ref "U2:A") (pin "45") (pinfunction "BDBUS6_45") (pintype "bidirectional+no_connect"))
    )
    (net (code "56") (name "unconnected-(U2:A-BDBUS7-Pad46)") (class "Default")
      (node (ref "U2:A") (pin "46") (pinfunction "BDBUS7_46") (pintype "bidirectional+no_connect"))
    )
    (net (code "57") (name "unconnected-(U3:A-NC-Pad2)") (class "Default")
      (node (ref "U3:A") (pin "2") (pinfunction "NC_2") (pintype "passive+no_connect"))
    )
    (net (code "58") (name "unconnected-(U4:A-NC-Pad7)") (class "Default")
      (node (ref "U4:A") (pin "7") (pinfunction "NC_7") (pintype "passive+no_connect"))
    )
  )
)
